# GMRpcb.net
KiCad netlist of a schematic drawn in Altium Designer
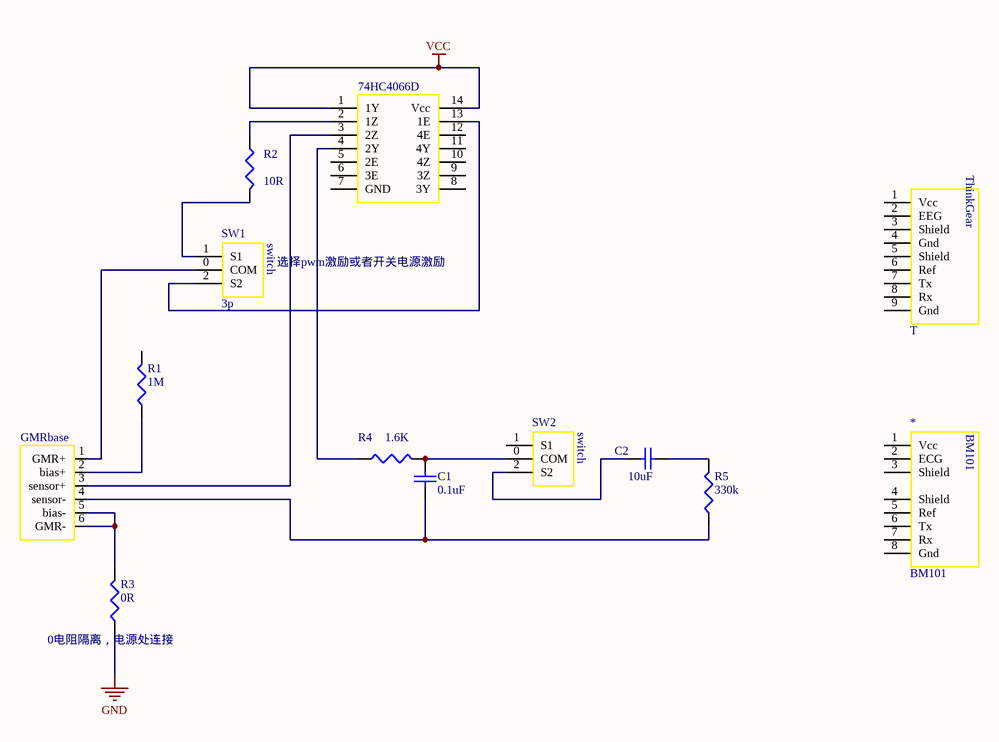
[diagram p0: GMRpcb.SchDoc]

(export (version "E")
  (design (tool "Eeschema 10.0.6"))
  (components
    (comp (ref "*") (value "BM101") (footprint "BM101") (libsource (lib "neurosky") (part "BM101")))
    (comp (ref "74HC4066")
      (value "74HC4066D")
      (footprint "74HC4066D")
      (libsource (lib "74HC") (part "74HC4066D"))
    )
    (comp (ref "C1")
      (value "cap0402")
      (footprint "cap0402")
      (fields (field (name "ALTIUM_UNNAMED_1") "0.1uF"))
      (libsource (lib "caplib") (part "cap0402"))
    )
    (comp (ref "C2")
      (value "cap0402")
      (footprint "cap0402")
      (fields (field (name "ALTIUM_UNNAMED_1") "10uF"))
      (libsource (lib "caplib") (part "cap0402"))
    )
    (comp (ref "GMRbase")
      (value "GMRbase")
      (footprint "GMRbase")
      (libsource (lib "GMRsensor") (part "GMRbase"))
    )
    (comp (ref "R1")
      (value "R")
      (footprint "res0402")
      (fields (field (name "ALTIUM_UNNAMED_1") "1M"))
      (libsource (lib "reslib") (part "res0402"))
    )
    (comp (ref "R2")
      (value "R")
      (footprint "res0402")
      (fields (field (name "ALTIUM_UNNAMED_1") "10R"))
      (libsource (lib "reslib") (part "res0402"))
    )
    (comp (ref "R3")
      (value "R")
      (footprint "res0402")
      (fields (field (name "ALTIUM_UNNAMED_1") "0R"))
      (libsource (lib "reslib") (part "res0402"))
    )
    (comp (ref "R4")
      (value "R")
      (footprint "res0402")
      (fields (field (name "ALTIUM_UNNAMED_1") "1.6K"))
      (libsource (lib "reslib") (part "res0402"))
    )
    (comp (ref "R5")
      (value "R")
      (footprint "res0402")
      (fields (field (name "ALTIUM_UNNAMED_1") "330k"))
      (libsource (lib "reslib") (part "res0402"))
    )
    (comp (ref "SW1") (value "3p") (footprint "3p") (libsource (lib "switch") (part "3p")))
    (comp (ref "SW2") (value "3p") (footprint "3p") (libsource (lib "switch") (part "3p")))
    (comp (ref "T")
      (value "ThinkGear")
      (footprint "ThinkGear")
      (libsource (lib "neurosky") (part "ThinkGear"))
    )
  )
  (nets
    (net (code "1") (name "GND") (class "Default")
      (node (ref "R3") (pin "1") (pinfunction "1_1") (pintype "passive"))
    )
    (net (code "2") (name "Net-(74HC4066-1E)") (class "Default")
      (node (ref "74HC4066") (pin "13") (pinfunction "1E_13") (pintype "passive"))
      (node (ref "SW1") (pin "2") (pinfunction "S2_2") (pintype "passive"))
    )
    (net (code "3") (name "Net-(74HC4066-1Z)") (class "Default")
      (node (ref "74HC4066") (pin "2") (pinfunction "1Z_2") (pintype "passive"))
      (node (ref "R2") (pin "1") (pinfunction "1_1") (pintype "passive"))
    )
    (net (code "4") (name "Net-(74HC4066-2Y)") (class "Default")
      (node (ref "74HC4066") (pin "4") (pinfunction "2Y_4") (pintype "passive"))
      (node (ref "R4") (pin "1") (pinfunction "1_1") (pintype "passive"))
    )
    (net (code "5") (name "Net-(74HC4066-2Z)") (class "Default")
      (node (ref "74HC4066") (pin "3") (pinfunction "2Z_3") (pintype "passive"))
      (node (ref "GMRbase") (pin "3") (pinfunction "sensor+_3") (pintype "passive"))
    )
    (net (code "6") (name "Net-(C2-Pad2)") (class "Default")
      (node (ref "C2") (pin "2") (pinfunction "2_2") (pintype "passive"))
      (node (ref "R5") (pin "2") (pinfunction "2_2") (pintype "passive"))
    )
    (net (code "7") (name "Net-(GMRbase-GMR+)") (class "Default")
      (node (ref "GMRbase") (pin "1") (pinfunction "GMR+_1") (pintype "passive"))
      (node (ref "SW1") (pin "0") (pinfunction "COM_0") (pintype "passive"))
    )
    (net (code "8") (name "Net-(GMRbase-GMR-)") (class "Default")
      (node (ref "GMRbase") (pin "5") (pinfunction "bias-_5") (pintype "passive"))
      (node (ref "GMRbase") (pin "6") (pinfunction "GMR-_6") (pintype "passive"))
      (node (ref "R3") (pin "2") (pinfunction "2_2") (pintype "passive"))
    )
    (net (code "9") (name "Net-(GMRbase-bias+)") (class "Default")
      (node (ref "GMRbase") (pin "2") (pinfunction "bias+_2") (pintype "passive"))
      (node (ref "R1") (pin "1") (pinfunction "1_1") (pintype "passive"))
    )
    (net (code "10") (name "Net-(GMRbase-sensor-)") (class "Default")
      (node (ref "C1") (pin "1") (pinfunction "1_1") (pintype "passive"))
      (node (ref "GMRbase") (pin "4") (pinfunction "sensor-_4") (pintype "passive"))
      (node (ref "R5") (pin "1") (pinfunction "1_1") (pintype "passive"))
    )
    (net (code "11") (name "Net-(SW1-S1)") (class "Default")
      (node (ref "R2") (pin "2") (pinfunction "2_2") (pintype "passive"))
      (node (ref "SW1") (pin "1") (pinfunction "S1_1") (pintype "passive"))
    )
    (net (code "12") (name "Net-(SW2-COM)") (class "Default")
      (node (ref "C1") (pin "2") (pinfunction "2_2") (pintype "passive"))
      (node (ref "R4") (pin "2") (pinfunction "2_2") (pintype "passive"))
      (node (ref "SW2") (pin "0") (pinfunction "COM_0") (pintype "passive"))
    )
    (net (code "13") (name "Net-(SW2-S2)") (class "Default")
      (node (ref "C2") (pin "1") (pinfunction "1_1") (pintype "passive"))
      (node (ref "SW2") (pin "2") (pinfunction "S2_2") (pintype "passive"))
    )
    (net (code "14") (name "VCC") (class "Default")
      (node (ref "74HC4066") (pin "1") (pinfunction "1Y_1") (pintype "passive"))
      (node (ref "74HC4066") (pin "14") (pinfunction "Vcc_14") (pintype "passive"))
    )
    (net (code "15") (name "unconnected-(*-ECG-Pad2)") (class "Default")
      (node (ref "*") (pin "2") (pinfunction "ECG_2") (pintype "passive"))
    )
    (net (code "16") (name "unconnected-(*-Gnd-Pad8)") (class "Default")
      (node (ref "*") (pin "8") (pinfunction "Gnd_8") (pintype "passive"))
    )
    (net (code "17") (name "unconnected-(*-Ref-Pad5)") (class "Default")
      (node (ref "*") (pin "5") (pinfunction "Ref_5") (pintype "passive"))
    )
    (net (code "18") (name "unconnected-(*-Rx-Pad7)") (class "Default")
      (node (ref "*") (pin "7") (pinfunction "Rx_7") (pintype "passive"))
    )
    (net (code "19") (name "unconnected-(*-Shield-Pad3)") (class "Default")
      (node (ref "*") (pin "3") (pinfunction "Shield_3") (pintype "passive"))
    )
    (net (code "20") (name "unconnected-(*-Shield-Pad4)") (class "Default")
      (node (ref "*") (pin "4") (pinfunction "Shield_4") (pintype "passive"))
    )
    (net (code "21") (name "unconnected-(*-Tx-Pad6)") (class "Default")
      (node (ref "*") (pin "6") (pinfunction "Tx_6") (pintype "passive"))
    )
    (net (code "22") (name "unconnected-(*-Vcc-Pad1)") (class "Default")
      (node (ref "*") (pin "1") (pinfunction "Vcc_1") (pintype "passive"))
    )
    (net (code "23") (name "unconnected-(74HC4066-2E-Pad5)") (class "Default")
      (node (ref "74HC4066") (pin "5") (pinfunction "2E_5") (pintype "passive"))
    )
    (net (code "24") (name "unconnected-(74HC4066-3E-Pad6)") (class "Default")
      (node (ref "74HC4066") (pin "6") (pinfunction "3E_6") (pintype "passive"))
    )
    (net (code "25") (name "unconnected-(74HC4066-3Y-Pad8)") (class "Default")
      (node (ref "74HC4066") (pin "8") (pinfunction "3Y_8") (pintype "passive"))
    )
    (net (code "26") (name "unconnected-(74HC4066-3Z-Pad9)") (class "Default")
      (node (ref "74HC4066") (pin "9") (pinfunction "3Z_9") (pintype "passive"))
    )
    (net (code "27") (name "unconnected-(74HC4066-4E-Pad12)") (class "Default")
      (node (ref "74HC4066") (pin "12") (pinfunction "4E_12") (pintype "passive"))
    )
    (net (code "28") (name "unconnected-(74HC4066-4Y-Pad11)") (class "Default")
      (node (ref "74HC4066") (pin "11") (pinfunction "4Y_11") (pintype "passive"))
    )
    (net (code "29") (name "unconnected-(74HC4066-4Z-Pad10)") (class "Default")
      (node (ref "74HC4066") (pin "10") (pinfunction "4Z_10") (pintype "passive"))
    )
    (net (code "30") (name "unconnected-(74HC4066-GND-Pad7)") (class "Default")
      (node (ref "74HC4066") (pin "7") (pinfunction "GND_7") (pintype "passive"))
    )
    (net (code "31") (name "unconnected-(R1-Pad2)") (class "Default")
      (node (ref "R1") (pin "2") (pinfunction "2_2") (pintype "passive"))
    )
    (net (code "32") (name "unconnected-(SW2-S1-Pad1)") (class "Default")
      (node (ref "SW2") (pin "1") (pinfunction "S1_1") (pintype "passive"))
    )
    (net (code "33") (name "unconnected-(T-EEG-Pad2)") (class "Default")
      (node (ref "T") (pin "2") (pinfunction "EEG_2") (pintype "passive"))
    )
    (net (code "34") (name "unconnected-(T-Gnd-Pad4)") (class "Default")
      (node (ref "T") (pin "4") (pinfunction "Gnd_4") (pintype "passive"))
    )
    (net (code "35") (name "unconnected-(T-Gnd-Pad9)") (class "Default")
      (node (ref "T") (pin "9") (pinfunction "Gnd_9") (pintype "passive"))
    )
    (net (code "36") (name "unconnected-(T-Ref-Pad6)") (class "Default")
      (node (ref "T") (pin "6") (pinfunction "Ref_6") (pintype "passive"))
    )
    (net (code "37") (name "unconnected-(T-Rx-Pad8)") (class "Default")
      (node (ref "T") (pin "8") (pinfunction "Rx_8") (pintype "passive"))
    )
    (net (code "38") (name "unconnected-(T-Shield-Pad3)") (class "Default")
      (node (ref "T") (pin "3") (pinfunction "Shield_3") (pintype "passive"))
    )
    (net (code "39") (name "unconnected-(T-Shield-Pad5)") (class "Default")
      (node (ref "T") (pin "5") (pinfunction "Shield_5") (pintype "passive"))
    )
    (net (code "40") (name "unconnected-(T-Tx-Pad7)") (class "Default")
      (node (ref "T") (pin "7") (pinfunction "Tx_7") (pintype "passive"))
    )
    (net (code "41") (name "unconnected-(T-Vcc-Pad1)") (class "Default")
      (node (ref "T") (pin "1") (pinfunction "Vcc_1") (pintype "passive"))
    )
  )
)
